# motor_driver.net
KiCad netlist of a schematic drawn in EAGLE
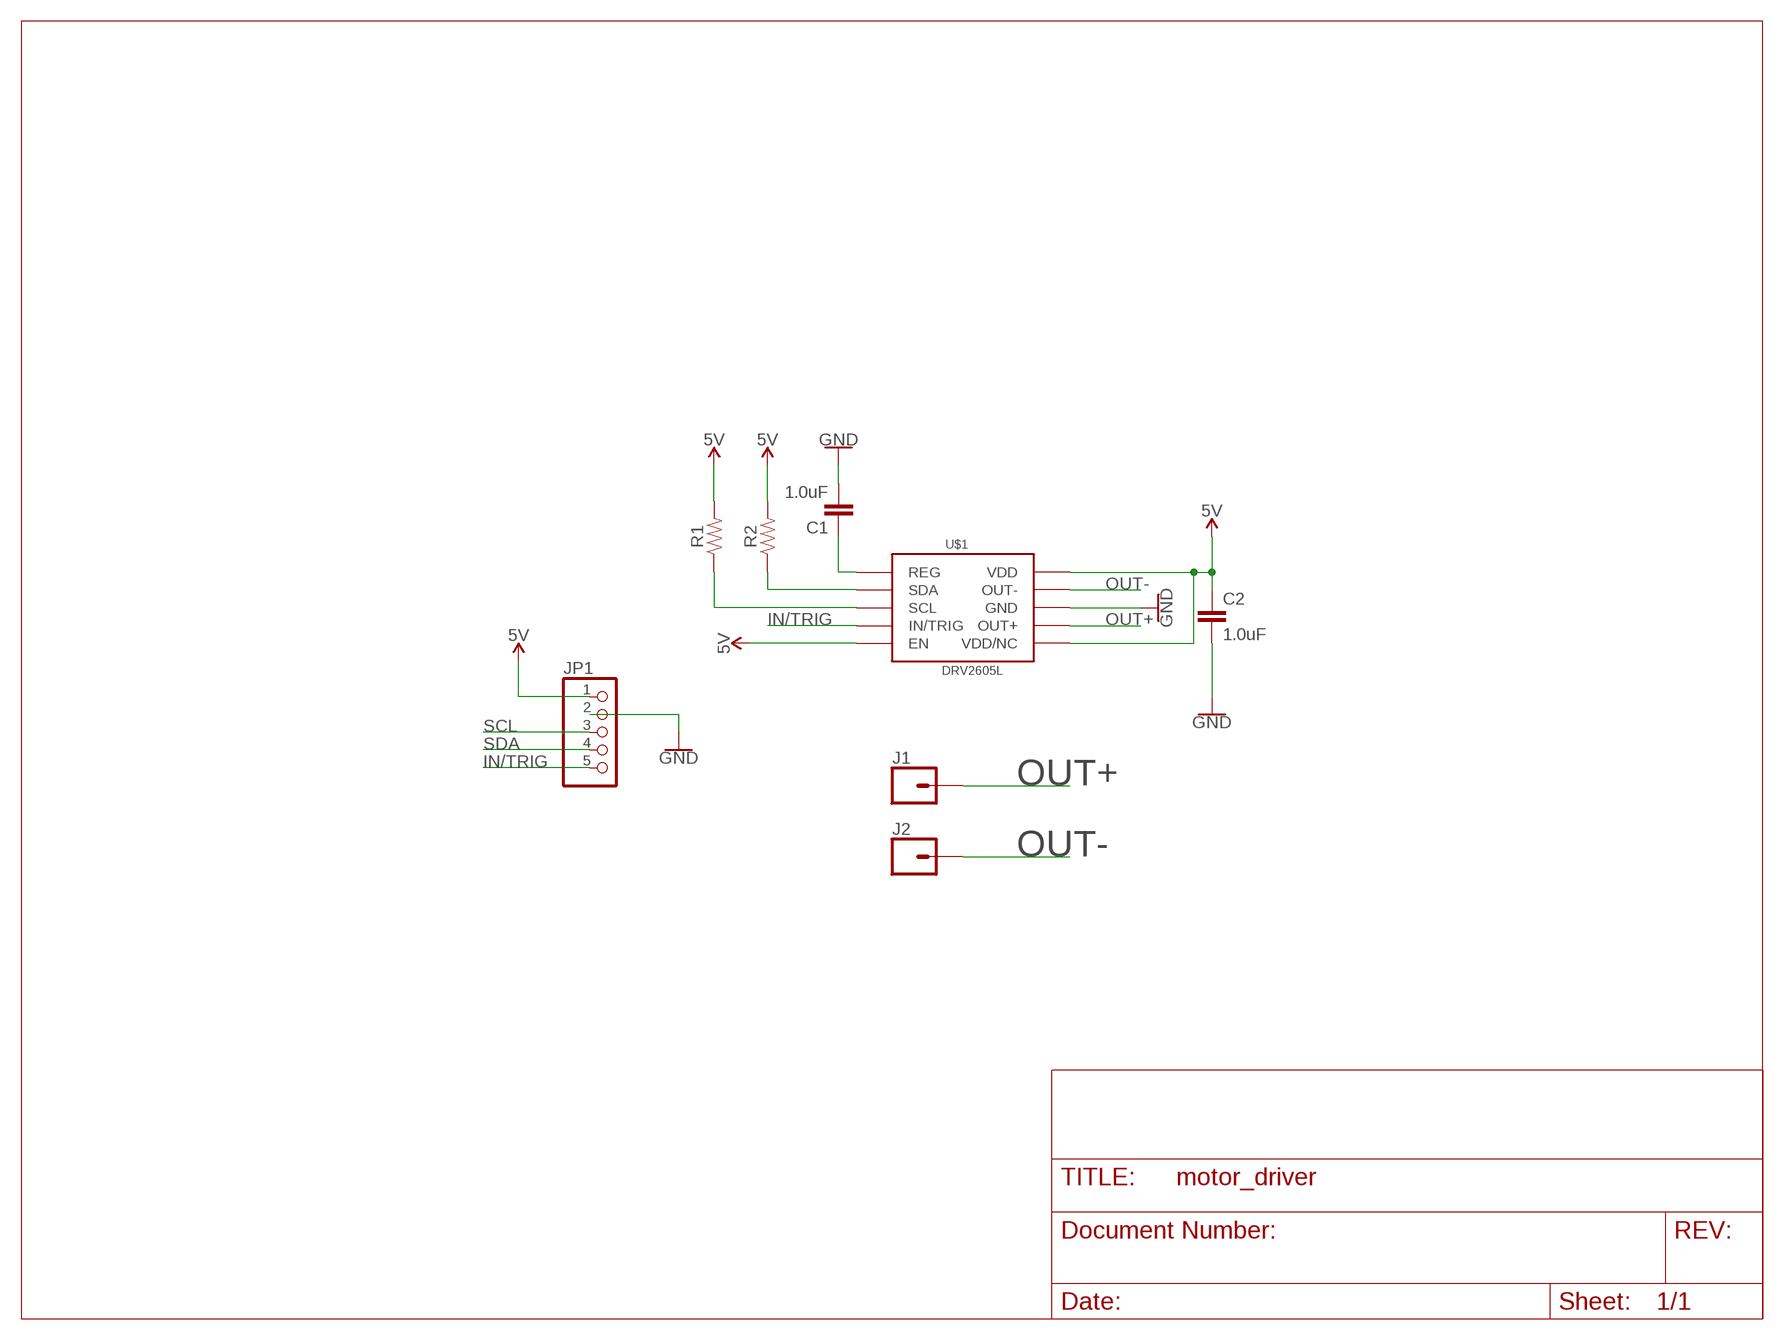
[diagram p0: schematic, sheet 1]

(export (version "E")
  (design (tool "Eeschema 10.0.6"))
  (components
    (comp (ref "C1")
      (value "1.0uF")
      (footprint "eagle-import:0805")
      (libsource (lib "eagle-import") (part "1.0UF-0805-25V-(+80/-20%)"))
    )
    (comp (ref "C2")
      (value "1.0uF")
      (footprint "eagle-import:0805")
      (libsource (lib "eagle-import") (part "1.0UF-0805-25V-(+80/-20%)"))
    )
    (comp (ref "J1")
      (value "CONN_01OFFSET")
      (footprint "eagle-import:1X01_OFFSET")
      (libsource (lib "eagle-import") (part "CONN_01OFFSET"))
    )
    (comp (ref "J2")
      (value "CONN_01OFFSET")
      (footprint "eagle-import:1X01_OFFSET")
      (libsource (lib "eagle-import") (part "CONN_01OFFSET"))
    )
    (comp (ref "JP1")
      (value "PINHD-1X5")
      (footprint "eagle-import:1X05")
      (libsource (lib "eagle-import") (part "PINHD-1X5"))
    )
    (comp (ref "R1")
      (value "RESISTOR0805")
      (footprint "eagle-import:0805")
      (libsource (lib "eagle-import") (part "RESISTOR0805"))
    )
    (comp (ref "R2")
      (value "RESISTOR0805")
      (footprint "eagle-import:0805")
      (libsource (lib "eagle-import") (part "RESISTOR0805"))
    )
    (comp (ref "U$1")
      (value "DRV2605L")
      (footprint "eagle-import:VSSOP-10")
      (libsource (lib "eagle-import") (part "DRV2605L"))
    )
  )
  (nets
    (net (code "1") (name "/IN{slash}TRIG") (class "Default")
      (node (ref "JP1") (pin "5") (pinfunction "5_5") (pintype "passive"))
      (node (ref "U$1") (pin "P$4") (pinfunction "IN/TRIG_P$4") (pintype "bidirectional"))
    )
    (net (code "2") (name "/OUT+") (class "Default")
      (node (ref "J1") (pin "1") (pinfunction "1_1") (pintype "passive"))
      (node (ref "U$1") (pin "P$7") (pinfunction "OUT+_P$7") (pintype "bidirectional"))
    )
    (net (code "3") (name "/OUT-") (class "Default")
      (node (ref "J2") (pin "1") (pinfunction "1_1") (pintype "passive"))
      (node (ref "U$1") (pin "P$9") (pinfunction "OUT-_P$9") (pintype "bidirectional"))
    )
    (net (code "4") (name "/SCL") (class "Default")
      (node (ref "JP1") (pin "3") (pinfunction "3_3") (pintype "passive"))
      (node (ref "R1") (pin "1") (pinfunction "1_1") (pintype "passive"))
      (node (ref "U$1") (pin "P$2") (pinfunction "SCL_P$2") (pintype "bidirectional"))
    )
    (net (code "5") (name "/SDA") (class "Default")
      (node (ref "JP1") (pin "4") (pinfunction "4_4") (pintype "passive"))
      (node (ref "R2") (pin "1") (pinfunction "1_1") (pintype "passive"))
      (node (ref "U$1") (pin "P$3") (pinfunction "SDA_P$3") (pintype "bidirectional"))
    )
    (net (code "6") (name "5V") (class "Default")
      (node (ref "C2") (pin "1") (pinfunction "1_1") (pintype "passive"))
      (node (ref "JP1") (pin "1") (pinfunction "1_1") (pintype "passive"))
      (node (ref "R1") (pin "2") (pinfunction "2_2") (pintype "passive"))
      (node (ref "R2") (pin "2") (pinfunction "2_2") (pintype "passive"))
      (node (ref "U$1") (pin "P$10") (pinfunction "VDD_P$10") (pintype "bidirectional"))
      (node (ref "U$1") (pin "P$5") (pinfunction "EN_P$5") (pintype "bidirectional"))
      (node (ref "U$1") (pin "P$6") (pinfunction "VDD/NC_P$6") (pintype "bidirectional"))
    )
    (net (code "7") (name "GND") (class "Default")
      (node (ref "C1") (pin "2") (pinfunction "2_2") (pintype "passive"))
      (node (ref "C2") (pin "2") (pinfunction "2_2") (pintype "passive"))
      (node (ref "JP1") (pin "2") (pinfunction "2_2") (pintype "passive"))
      (node (ref "U$1") (pin "P$8") (pinfunction "GND_P$8") (pintype "bidirectional"))
    )
    (net (code "8") (name "Net-(U$1-REG)") (class "Default")
      (node (ref "C1") (pin "1") (pinfunction "1_1") (pintype "passive"))
      (node (ref "U$1") (pin "P$1") (pinfunction "REG_P$1") (pintype "bidirectional"))
    )
  )
)
